# MCU_Schematic.net
KiCad netlist of a schematic drawn in Altium Designer
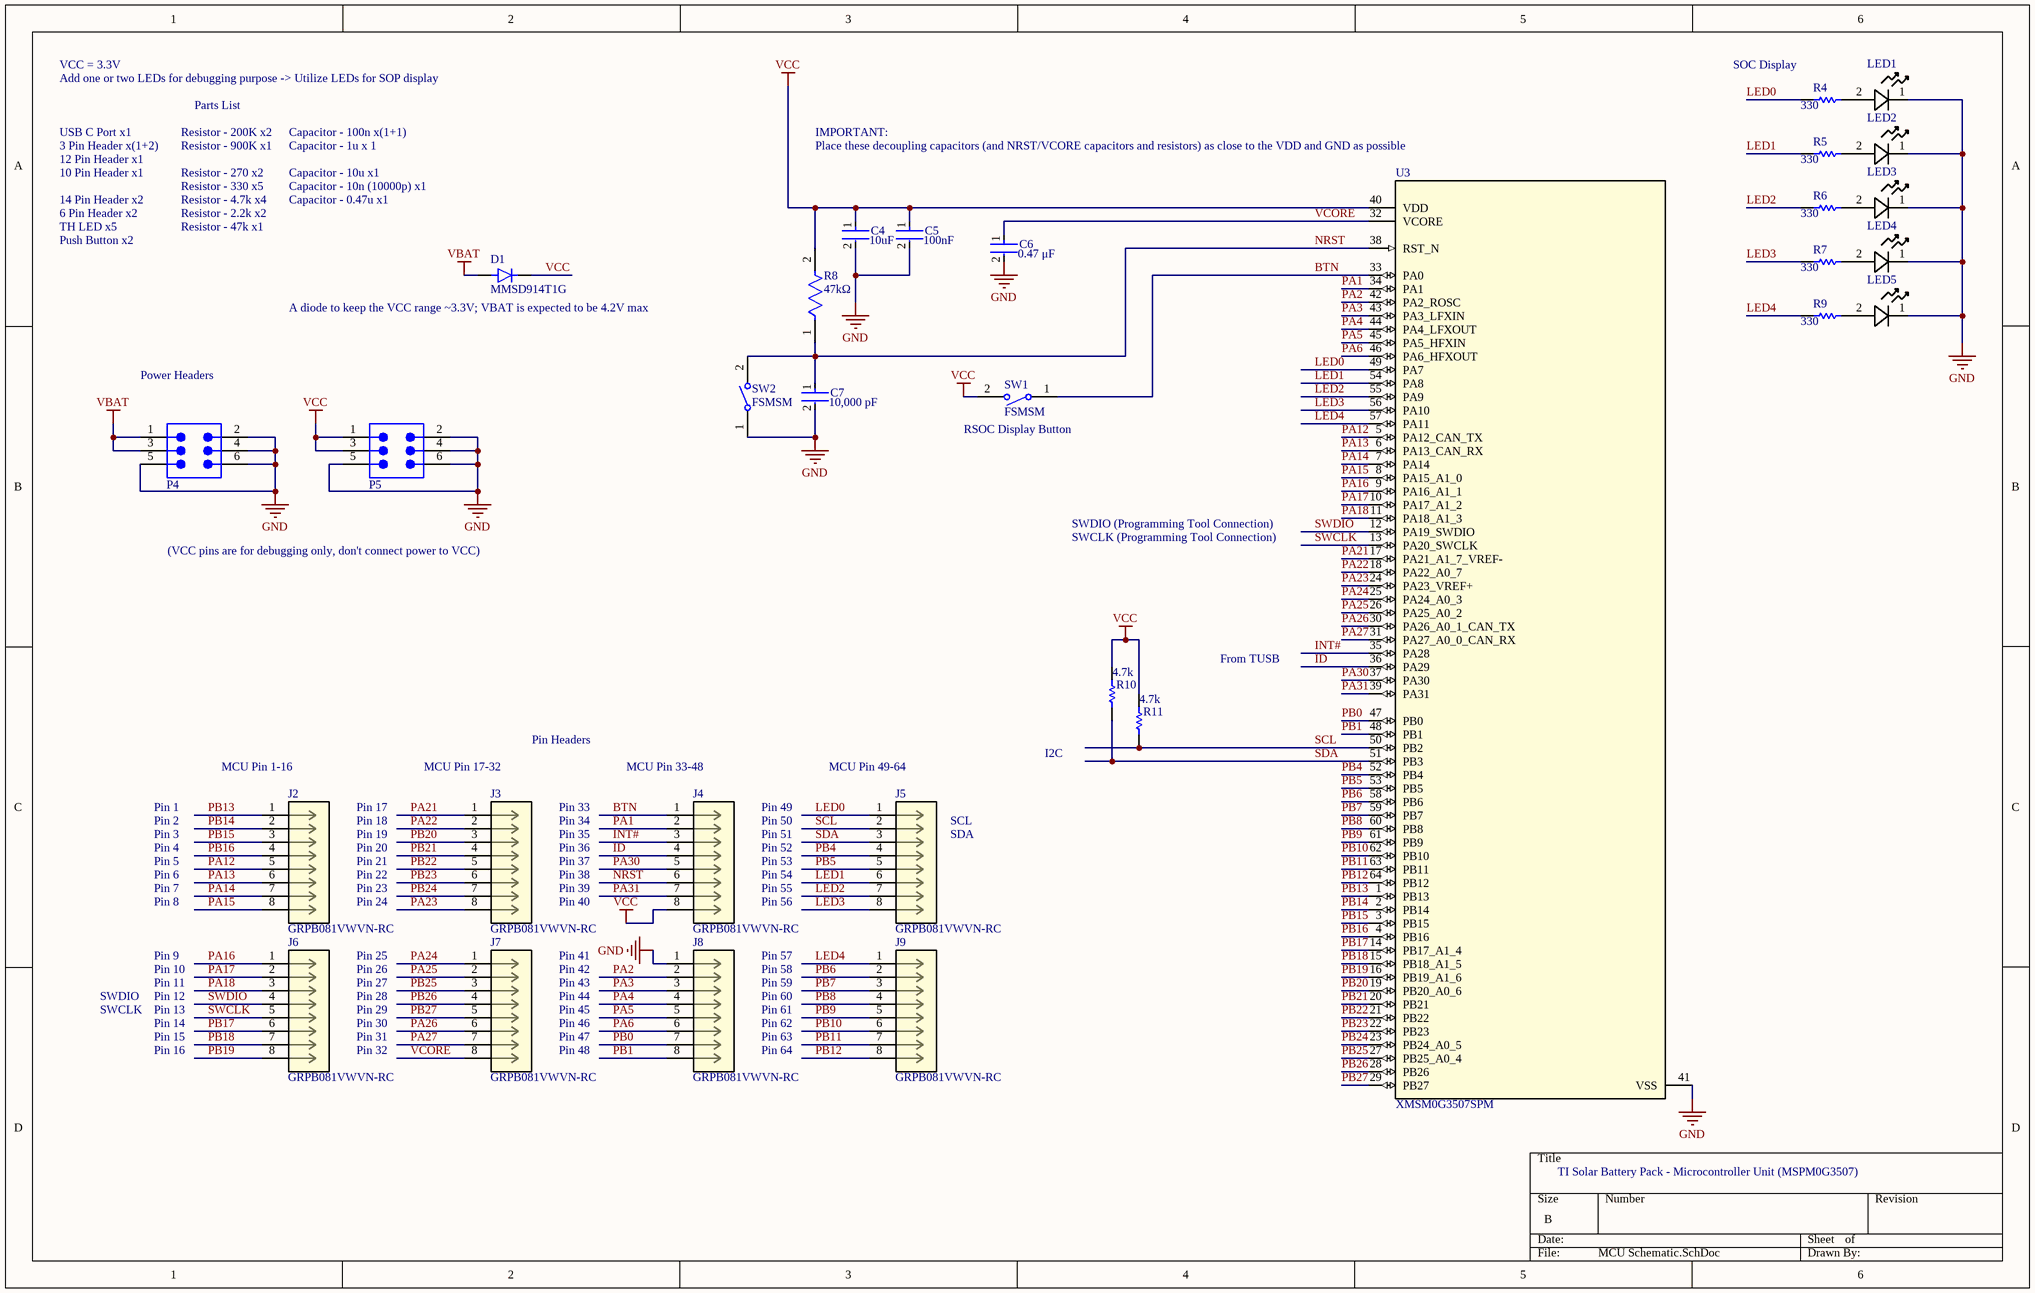
[diagram p0: MCU Schematic.SchDoc]

(export (version "E")
  (design (tool "Eeschema 10.0.6"))
  (components
    (comp (ref "C4")
      (value "C0805C106J8RACAUTO")
      (footprint "FP-C0805C106J8RACAUTO-MFG")
      (description "CAP CER 10UF 10V X7R 0805")
      (fields (field (name "CAPACITANCE") "10uF") (field (name "TOLERANCE") "5%"))
      (libsource (lib "Altium Content Vault") (part "02cd4be3c70576c341d710602a673aa"))
    )
    (comp (ref "C5")
      (value "GRMJN65C1H104GE01J")
      (footprint "FP-GRMJN6-0_1-MFG")
      (description "GRMJN65C1H104GE01J Multilayer Ceramic Capacitor, 0.1 uF, 50 V, ± 2%, C0G (NP0), 0704 [1810 Metric]")
      (fields (field (name "TOLERANCE") "2%") (field (name "CAPACITANCE") "100nF"))
      (libsource (lib "Altium Content Vault") (part "02cd4be3c70576c341d710602a673aa"))
    )
    (comp (ref "C6")
      (value "0.47 μF")
      (footprint "FP-C0603C-CF-MFG")
      (description "CAP CER 0.47UF 16V X7R 0603")
      (fields
        (field (name "MANUFACTURER PART NUMBER") "C0603C474J4RACTU")
        (field (name "MANUFACTURER") "KEMET")
      )
      (libsource (lib "Altium Content Vault") (part "b4654b650e69147ec39a6b967a45e02"))
    )
    (comp (ref "C7")
      (value "10,000 pF")
      (footprint "FP-C0603C-CF-MFG")
      (description "Capacitor; Ceramic; Cap; .010uF; Tol 5%; SMT; Vol-Rtg 50V; X7R; Tape and Reel")
      (fields
        (field (name "OCTOPART") "https://octopart.com/c0603c103j5ractu-kemet-91371")
        (field (name "MANUFACTURER") "KEMET")
      )
      (libsource (lib "Altium Content Vault") (part "b4654b650e69147ec39a6b967a45e02"))
    )
    (comp (ref "D1")
      (value "MMSD914T1G")
      (footprint "DIO_MMSD914T1G")
      (description "Diode Standard 100 V 200mA (DC) Surface Mount SOD-123")
      (fields (field (name "MF") "ON Semiconductor"))
      (libsource (lib "MMSD914T1G") (part "MMSD914T1G"))
    )
    (comp (ref "J2")
      (value "GRPB081VWVN-RC")
      (footprint "CONN8_VWVN-RC_SUL")
      (description "No Description Available")
      (libsource (lib "GRPB081VWVN-RC") (part "GRPB081VWVN-RC"))
    )
    (comp (ref "J3")
      (value "GRPB081VWVN-RC")
      (footprint "CONN8_VWVN-RC_SUL")
      (description "No Description Available")
      (libsource (lib "GRPB081VWVN-RC") (part "GRPB081VWVN-RC"))
    )
    (comp (ref "J4")
      (value "GRPB081VWVN-RC")
      (footprint "CONN8_VWVN-RC_SUL")
      (description "No Description Available")
      (libsource (lib "GRPB081VWVN-RC") (part "GRPB081VWVN-RC"))
    )
    (comp (ref "J5")
      (value "GRPB081VWVN-RC")
      (footprint "CONN8_VWVN-RC_SUL")
      (description "No Description Available")
      (libsource (lib "GRPB081VWVN-RC") (part "GRPB081VWVN-RC"))
    )
    (comp (ref "J6")
      (value "GRPB081VWVN-RC")
      (footprint "CONN8_VWVN-RC_SUL")
      (description "No Description Available")
      (libsource (lib "GRPB081VWVN-RC") (part "GRPB081VWVN-RC"))
    )
    (comp (ref "J7")
      (value "GRPB081VWVN-RC")
      (footprint "CONN8_VWVN-RC_SUL")
      (description "No Description Available")
      (libsource (lib "GRPB081VWVN-RC") (part "GRPB081VWVN-RC"))
    )
    (comp (ref "J8")
      (value "GRPB081VWVN-RC")
      (footprint "CONN8_VWVN-RC_SUL")
      (description "No Description Available")
      (libsource (lib "GRPB081VWVN-RC") (part "GRPB081VWVN-RC"))
    )
    (comp (ref "J9")
      (value "GRPB081VWVN-RC")
      (footprint "CONN8_VWVN-RC_SUL")
      (description "No Description Available")
      (libsource (lib "GRPB081VWVN-RC") (part "GRPB081VWVN-RC"))
    )
    (comp (ref "LED1")
      (value "LTW-420D7")
      (footprint "LED_LTW-420D7_LTO")
      (description "No Description Available")
      (libsource (lib "LTW-420D7") (part "LTW-420D7"))
    )
    (comp (ref "LED2")
      (value "LTW-420D7")
      (footprint "LED_LTW-420D7_LTO")
      (description "No Description Available")
      (libsource (lib "LTW-420D7") (part "LTW-420D7"))
    )
    (comp (ref "LED3")
      (value "LTW-420D7")
      (footprint "LED_LTW-420D7_LTO")
      (description "No Description Available")
      (libsource (lib "LTW-420D7") (part "LTW-420D7"))
    )
    (comp (ref "LED4")
      (value "LTW-420D7")
      (footprint "LED_LTW-420D7_LTO")
      (description "No Description Available")
      (libsource (lib "LTW-420D7") (part "LTW-420D7"))
    )
    (comp (ref "LED5")
      (value "LTW-420D7")
      (footprint "LED_LTW-420D7_LTO")
      (description "No Description Available")
      (libsource (lib "LTW-420D7") (part "LTW-420D7"))
    )
    (comp (ref "P4")
      (value "61000621121")
      (footprint "61000621121")
      (description "WR-PHD Pin Header, SMT, Vertical, pitch 2.54mm, 2 Row, 6P")
      (fields (field (name "MANUFACTURER") "Wurth Elektronik"))
      (libsource (lib "Altium_WR-PHD_rev24a") (part "61000621121"))
    )
    (comp (ref "P5")
      (value "61000621121")
      (footprint "61000621121")
      (description "WR-PHD Pin Header, SMT, Vertical, pitch 2.54mm, 2 Row, 6P")
      (fields (field (name "MANUFACTURER") "Wurth Elektronik"))
      (libsource (lib "Altium_WR-PHD_rev24a") (part "61000621121"))
    )
    (comp (ref "R4")
      (value "330")
      (footprint "RESC2013X60X40LL20T25")
      (fields (field (name "MANUFACTURER") "Panasonic") (field (name "PART NUMBER") "ERA6AEB331V"))
      (libsource (lib "Altium Content Vault") (part "RES"))
    )
    (comp (ref "R5")
      (value "330")
      (footprint "RESC2013X60X40LL20T25")
      (fields (field (name "MANUFACTURER") "Panasonic") (field (name "PART NUMBER") "ERA6AEB331V"))
      (libsource (lib "Altium Content Vault") (part "RES"))
    )
    (comp (ref "R6")
      (value "330")
      (footprint "RESC2013X60X40LL20T25")
      (fields (field (name "MANUFACTURER") "Panasonic") (field (name "PART NUMBER") "ERA6AEB331V"))
      (libsource (lib "Altium Content Vault") (part "RES"))
    )
    (comp (ref "R7")
      (value "330")
      (footprint "RESC2013X60X40LL20T25")
      (fields (field (name "MANUFACTURER") "Panasonic") (field (name "PART NUMBER") "ERA6AEB331V"))
      (libsource (lib "Altium Content Vault") (part "RES"))
    )
    (comp (ref "R8")
      (value "ERA-6AEB473V")
      (footprint "FP-ERA6A-MFG")
      (fields (field (name "RESISTANCE") "47kΩ") (field (name "TOLERANCE") "0.1%"))
      (libsource (lib "Altium Content Vault") (part "1029c3af85768c4190bb7ad29bc67b5"))
    )
    (comp (ref "R9")
      (value "330")
      (footprint "RESC2013X60X40LL20T25")
      (fields (field (name "MANUFACTURER") "Panasonic") (field (name "PART NUMBER") "ERA6AEB331V"))
      (libsource (lib "Altium Content Vault") (part "RES"))
    )
    (comp (ref "R10")
      (value "4.7k")
      (footprint "RESC2013X60X40ML20T25")
      (fields
        (field (name "PART NUMBER") "ERA6AEB472V")
        (field (name "MANUFACTURER") "Panasonic")
        (field (name "MANUFACTURER PART NUMBER") "ERA-6AEB472V")
      )
      (libsource (lib "Altium Content Vault") (part "RES"))
    )
    (comp (ref "R11")
      (value "4.7k")
      (footprint "RESC2013X60X40ML20T25")
      (fields
        (field (name "PART NUMBER") "ERA6AEB472V")
        (field (name "MANUFACTURER") "Panasonic")
        (field (name "MANUFACTURER PART NUMBER") "ERA-6AEB472V")
      )
      (libsource (lib "Altium Content Vault") (part "RES"))
    )
    (comp (ref "SW1")
      (value "FSMSM")
      (footprint "TECO-FSMSM-2_V")
      (description "FSMSM Push Button Switch, 50 mA, -35 to 85 degC, 2-Pin SMD, RoHS, Bulk")
      (fields (field (name "MANUFACTURER") "TE Connectivity"))
      (libsource (lib "Altium Content Vault") (part "SW-SPST-2_C"))
    )
    (comp (ref "SW2")
      (value "FSMSM")
      (footprint "TECO-FSMSM-2_V")
      (description "FSMSM Push Button Switch, 50 mA, -35 to 85 degC, 2-Pin SMD, RoHS, Bulk")
      (fields (field (name "MANUFACTURER") "TE Connectivity"))
      (libsource (lib "Altium Content Vault") (part "SW-SPST-2_C"))
    )
    (comp (ref "U3")
      (value "XMSM0G3507SPM")
      (footprint "PM0064A-IPC_A")
      (description "No Description Available")
      (libsource (lib "XMSM0G3507SPM") (part "XMSM0G3507SPM"))
    )
  )
  (nets
    (net (code "1") (name "/BTN") (class "Default")
      (node (ref "J4") (pin "1") (pinfunction "1_1") (pintype "passive"))
      (node (ref "SW1") (pin "1") (pinfunction "1_1") (pintype "passive"))
      (node (ref "U3") (pin "33") (pinfunction "PA0_33") (pintype "bidirectional"))
    )
    (net (code "2") (name "/ID") (class "Default")
      (node (ref "J4") (pin "4") (pinfunction "4_4") (pintype "passive"))
      (node (ref "U3") (pin "36") (pinfunction "PA29_36") (pintype "bidirectional"))
    )
    (net (code "3") (name "/INT#") (class "Default")
      (node (ref "J4") (pin "3") (pinfunction "3_3") (pintype "passive"))
      (node (ref "U3") (pin "35") (pinfunction "PA28_35") (pintype "bidirectional"))
    )
    (net (code "4") (name "/LED0") (class "Default")
      (node (ref "J5") (pin "1") (pinfunction "1_1") (pintype "passive"))
      (node (ref "R4") (pin "1") (pinfunction "1_1") (pintype "passive"))
      (node (ref "U3") (pin "49") (pinfunction "PA7_49") (pintype "bidirectional"))
    )
    (net (code "5") (name "/LED1") (class "Default")
      (node (ref "J5") (pin "6") (pinfunction "6_6") (pintype "passive"))
      (node (ref "R5") (pin "1") (pinfunction "1_1") (pintype "passive"))
      (node (ref "U3") (pin "54") (pinfunction "PA8_54") (pintype "bidirectional"))
    )
    (net (code "6") (name "/LED2") (class "Default")
      (node (ref "J5") (pin "7") (pinfunction "7_7") (pintype "passive"))
      (node (ref "R6") (pin "1") (pinfunction "1_1") (pintype "passive"))
      (node (ref "U3") (pin "55") (pinfunction "PA9_55") (pintype "bidirectional"))
    )
    (net (code "7") (name "/LED3") (class "Default")
      (node (ref "J5") (pin "8") (pinfunction "8_8") (pintype "passive"))
      (node (ref "R7") (pin "1") (pinfunction "1_1") (pintype "passive"))
      (node (ref "U3") (pin "56") (pinfunction "PA10_56") (pintype "bidirectional"))
    )
    (net (code "8") (name "/LED4") (class "Default")
      (node (ref "J9") (pin "1") (pinfunction "1_1") (pintype "passive"))
      (node (ref "R9") (pin "1") (pinfunction "1_1") (pintype "passive"))
      (node (ref "U3") (pin "57") (pinfunction "PA11_57") (pintype "bidirectional"))
    )
    (net (code "9") (name "/NRST") (class "Default")
      (node (ref "C7") (pin "1") (pinfunction "1_1") (pintype "passive"))
      (node (ref "J4") (pin "6") (pinfunction "6_6") (pintype "passive"))
      (node (ref "R8") (pin "1") (pinfunction "1_1") (pintype "passive"))
      (node (ref "SW2") (pin "2") (pinfunction "2_2") (pintype "passive"))
      (node (ref "U3") (pin "38") (pinfunction "RST_N_38") (pintype "input"))
    )
    (net (code "10") (name "/PA1") (class "Default")
      (node (ref "J4") (pin "2") (pinfunction "2_2") (pintype "passive"))
      (node (ref "U3") (pin "34") (pinfunction "PA1_34") (pintype "bidirectional"))
    )
    (net (code "11") (name "/PA2") (class "Default")
      (node (ref "J8") (pin "2") (pinfunction "2_2") (pintype "passive"))
      (node (ref "U3") (pin "42") (pinfunction "PA2_ROSC_42") (pintype "bidirectional"))
    )
    (net (code "12") (name "/PA3") (class "Default")
      (node (ref "J8") (pin "3") (pinfunction "3_3") (pintype "passive"))
      (node (ref "U3") (pin "43") (pinfunction "PA3_LFXIN_43") (pintype "bidirectional"))
    )
    (net (code "13") (name "/PA4") (class "Default")
      (node (ref "J8") (pin "4") (pinfunction "4_4") (pintype "passive"))
      (node (ref "U3") (pin "44") (pinfunction "PA4_LFXOUT_44") (pintype "bidirectional"))
    )
    (net (code "14") (name "/PA5") (class "Default")
      (node (ref "J8") (pin "5") (pinfunction "5_5") (pintype "passive"))
      (node (ref "U3") (pin "45") (pinfunction "PA5_HFXIN_45") (pintype "bidirectional"))
    )
    (net (code "15") (name "/PA6") (class "Default")
      (node (ref "J8") (pin "6") (pinfunction "6_6") (pintype "passive"))
      (node (ref "U3") (pin "46") (pinfunction "PA6_HFXOUT_46") (pintype "bidirectional"))
    )
    (net (code "16") (name "/PA12") (class "Default")
      (node (ref "J2") (pin "5") (pinfunction "5_5") (pintype "passive"))
      (node (ref "U3") (pin "5") (pinfunction "PA12_CAN_TX_5") (pintype "bidirectional"))
    )
    (net (code "17") (name "/PA13") (class "Default")
      (node (ref "J2") (pin "6") (pinfunction "6_6") (pintype "passive"))
      (node (ref "U3") (pin "6") (pinfunction "PA13_CAN_RX_6") (pintype "bidirectional"))
    )
    (net (code "18") (name "/PA14") (class "Default")
      (node (ref "J2") (pin "7") (pinfunction "7_7") (pintype "passive"))
      (node (ref "U3") (pin "7") (pinfunction "PA14_7") (pintype "bidirectional"))
    )
    (net (code "19") (name "/PA15") (class "Default")
      (node (ref "J2") (pin "8") (pinfunction "8_8") (pintype "passive"))
      (node (ref "U3") (pin "8") (pinfunction "PA15_A1_0_8") (pintype "bidirectional"))
    )
    (net (code "20") (name "/PA16") (class "Default")
      (node (ref "J6") (pin "1") (pinfunction "1_1") (pintype "passive"))
      (node (ref "U3") (pin "9") (pinfunction "PA16_A1_1_9") (pintype "bidirectional"))
    )
    (net (code "21") (name "/PA17") (class "Default")
      (node (ref "J6") (pin "2") (pinfunction "2_2") (pintype "passive"))
      (node (ref "U3") (pin "10") (pinfunction "PA17_A1_2_10") (pintype "bidirectional"))
    )
    (net (code "22") (name "/PA18") (class "Default")
      (node (ref "J6") (pin "3") (pinfunction "3_3") (pintype "passive"))
      (node (ref "U3") (pin "11") (pinfunction "PA18_A1_3_11") (pintype "bidirectional"))
    )
    (net (code "23") (name "/PA21") (class "Default")
      (node (ref "J3") (pin "1") (pinfunction "1_1") (pintype "passive"))
      (node (ref "U3") (pin "17") (pinfunction "PA21_A1_7_VREF-_17") (pintype "bidirectional"))
    )
    (net (code "24") (name "/PA22") (class "Default")
      (node (ref "J3") (pin "2") (pinfunction "2_2") (pintype "passive"))
      (node (ref "U3") (pin "18") (pinfunction "PA22_A0_7_18") (pintype "bidirectional"))
    )
    (net (code "25") (name "/PA23") (class "Default")
      (node (ref "J3") (pin "8") (pinfunction "8_8") (pintype "passive"))
      (node (ref "U3") (pin "24") (pinfunction "PA23_VREF+_24") (pintype "bidirectional"))
    )
    (net (code "26") (name "/PA24") (class "Default")
      (node (ref "J7") (pin "1") (pinfunction "1_1") (pintype "passive"))
      (node (ref "U3") (pin "25") (pinfunction "PA24_A0_3_25") (pintype "bidirectional"))
    )
    (net (code "27") (name "/PA25") (class "Default")
      (node (ref "J7") (pin "2") (pinfunction "2_2") (pintype "passive"))
      (node (ref "U3") (pin "26") (pinfunction "PA25_A0_2_26") (pintype "bidirectional"))
    )
    (net (code "28") (name "/PA26") (class "Default")
      (node (ref "J7") (pin "6") (pinfunction "6_6") (pintype "passive"))
      (node (ref "U3") (pin "30") (pinfunction "PA26_A0_1_CAN_TX_30") (pintype "bidirectional"))
    )
    (net (code "29") (name "/PA27") (class "Default")
      (node (ref "J7") (pin "7") (pinfunction "7_7") (pintype "passive"))
      (node (ref "U3") (pin "31") (pinfunction "PA27_A0_0_CAN_RX_31") (pintype "bidirectional"))
    )
    (net (code "30") (name "/PA30") (class "Default")
      (node (ref "J4") (pin "5") (pinfunction "5_5") (pintype "passive"))
      (node (ref "U3") (pin "37") (pinfunction "PA30_37") (pintype "bidirectional"))
    )
    (net (code "31") (name "/PA31") (class "Default")
      (node (ref "J4") (pin "7") (pinfunction "7_7") (pintype "passive"))
      (node (ref "U3") (pin "39") (pinfunction "PA31_39") (pintype "bidirectional"))
    )
    (net (code "32") (name "/PB0") (class "Default")
      (node (ref "J8") (pin "7") (pinfunction "7_7") (pintype "passive"))
      (node (ref "U3") (pin "47") (pinfunction "PB0_47") (pintype "bidirectional"))
    )
    (net (code "33") (name "/PB1") (class "Default")
      (node (ref "J8") (pin "8") (pinfunction "8_8") (pintype "passive"))
      (node (ref "U3") (pin "48") (pinfunction "PB1_48") (pintype "bidirectional"))
    )
    (net (code "34") (name "/PB4") (class "Default")
      (node (ref "J5") (pin "4") (pinfunction "4_4") (pintype "passive"))
      (node (ref "U3") (pin "52") (pinfunction "PB4_52") (pintype "bidirectional"))
    )
    (net (code "35") (name "/PB5") (class "Default")
      (node (ref "J5") (pin "5") (pinfunction "5_5") (pintype "passive"))
      (node (ref "U3") (pin "53") (pinfunction "PB5_53") (pintype "bidirectional"))
    )
    (net (code "36") (name "/PB6") (class "Default")
      (node (ref "J9") (pin "2") (pinfunction "2_2") (pintype "passive"))
      (node (ref "U3") (pin "58") (pinfunction "PB6_58") (pintype "bidirectional"))
    )
    (net (code "37") (name "/PB7") (class "Default")
      (node (ref "J9") (pin "3") (pinfunction "3_3") (pintype "passive"))
      (node (ref "U3") (pin "59") (pinfunction "PB7_59") (pintype "bidirectional"))
    )
    (net (code "38") (name "/PB8") (class "Default")
      (node (ref "J9") (pin "4") (pinfunction "4_4") (pintype "passive"))
      (node (ref "U3") (pin "60") (pinfunction "PB8_60") (pintype "bidirectional"))
    )
    (net (code "39") (name "/PB9") (class "Default")
      (node (ref "J9") (pin "5") (pinfunction "5_5") (pintype "passive"))
      (node (ref "U3") (pin "61") (pinfunction "PB9_61") (pintype "bidirectional"))
    )
    (net (code "40") (name "/PB10") (class "Default")
      (node (ref "J9") (pin "6") (pinfunction "6_6") (pintype "passive"))
      (node (ref "U3") (pin "62") (pinfunction "PB10_62") (pintype "bidirectional"))
    )
    (net (code "41") (name "/PB11") (class "Default")
      (node (ref "J9") (pin "7") (pinfunction "7_7") (pintype "passive"))
      (node (ref "U3") (pin "63") (pinfunction "PB11_63") (pintype "bidirectional"))
    )
    (net (code "42") (name "/PB12") (class "Default")
      (node (ref "J9") (pin "8") (pinfunction "8_8") (pintype "passive"))
      (node (ref "U3") (pin "64") (pinfunction "PB12_64") (pintype "bidirectional"))
    )
    (net (code "43") (name "/PB13") (class "Default")
      (node (ref "J2") (pin "1") (pinfunction "1_1") (pintype "passive"))
      (node (ref "U3") (pin "1") (pinfunction "PB13_1") (pintype "bidirectional"))
    )
    (net (code "44") (name "/PB14") (class "Default")
      (node (ref "J2") (pin "2") (pinfunction "2_2") (pintype "passive"))
      (node (ref "U3") (pin "2") (pinfunction "PB14_2") (pintype "bidirectional"))
    )
    (net (code "45") (name "/PB15") (class "Default")
      (node (ref "J2") (pin "3") (pinfunction "3_3") (pintype "passive"))
      (node (ref "U3") (pin "3") (pinfunction "PB15_3") (pintype "bidirectional"))
    )
    (net (code "46") (name "/PB16") (class "Default")
      (node (ref "J2") (pin "4") (pinfunction "4_4") (pintype "passive"))
      (node (ref "U3") (pin "4") (pinfunction "PB16_4") (pintype "bidirectional"))
    )
    (net (code "47") (name "/PB17") (class "Default")
      (node (ref "J6") (pin "6") (pinfunction "6_6") (pintype "passive"))
      (node (ref "U3") (pin "14") (pinfunction "PB17_A1_4_14") (pintype "bidirectional"))
    )
    (net (code "48") (name "/PB18") (class "Default")
      (node (ref "J6") (pin "7") (pinfunction "7_7") (pintype "passive"))
      (node (ref "U3") (pin "15") (pinfunction "PB18_A1_5_15") (pintype "bidirectional"))
    )
    (net (code "49") (name "/PB19") (class "Default")
      (node (ref "J6") (pin "8") (pinfunction "8_8") (pintype "passive"))
      (node (ref "U3") (pin "16") (pinfunction "PB19_A1_6_16") (pintype "bidirectional"))
    )
    (net (code "50") (name "/PB20") (class "Default")
      (node (ref "J3") (pin "3") (pinfunction "3_3") (pintype "passive"))
      (node (ref "U3") (pin "19") (pinfunction "PB20_A0_6_19") (pintype "bidirectional"))
    )
    (net (code "51") (name "/PB21") (class "Default")
      (node (ref "J3") (pin "4") (pinfunction "4_4") (pintype "passive"))
      (node (ref "U3") (pin "20") (pinfunction "PB21_20") (pintype "bidirectional"))
    )
    (net (code "52") (name "/PB22") (class "Default")
      (node (ref "J3") (pin "5") (pinfunction "5_5") (pintype "passive"))
      (node (ref "U3") (pin "21") (pinfunction "PB22_21") (pintype "bidirectional"))
    )
    (net (code "53") (name "/PB23") (class "Default")
      (node (ref "J3") (pin "6") (pinfunction "6_6") (pintype "passive"))
      (node (ref "U3") (pin "22") (pinfunction "PB23_22") (pintype "bidirectional"))
    )
    (net (code "54") (name "/PB24") (class "Default")
      (node (ref "J3") (pin "7") (pinfunction "7_7") (pintype "passive"))
      (node (ref "U3") (pin "23") (pinfunction "PB24_A0_5_23") (pintype "bidirectional"))
    )
    (net (code "55") (name "/PB25") (class "Default")
      (node (ref "J7") (pin "3") (pinfunction "3_3") (pintype "passive"))
      (node (ref "U3") (pin "27") (pinfunction "PB25_A0_4_27") (pintype "bidirectional"))
    )
    (net (code "56") (name "/PB26") (class "Default")
      (node (ref "J7") (pin "4") (pinfunction "4_4") (pintype "passive"))
      (node (ref "U3") (pin "28") (pinfunction "PB26_28") (pintype "bidirectional"))
    )
    (net (code "57") (name "/PB27") (class "Default")
      (node (ref "J7") (pin "5") (pinfunction "5_5") (pintype "passive"))
      (node (ref "U3") (pin "29") (pinfunction "PB27_29") (pintype "bidirectional"))
    )
    (net (code "58") (name "/SCL") (class "Default")
      (node (ref "J5") (pin "2") (pinfunction "2_2") (pintype "passive"))
      (node (ref "R11") (pin "1") (pinfunction "1_1") (pintype "passive"))
      (node (ref "U3") (pin "50") (pinfunction "PB2_50") (pintype "bidirectional"))
    )
    (net (code "59") (name "/SDA") (class "Default")
      (node (ref "J5") (pin "3") (pinfunction "3_3") (pintype "passive"))
      (node (ref "R10") (pin "1") (pinfunction "1_1") (pintype "passive"))
      (node (ref "U3") (pin "51") (pinfunction "PB3_51") (pintype "bidirectional"))
    )
    (net (code "60") (name "/SWCLK") (class "Default")
      (node (ref "J6") (pin "5") (pinfunction "5_5") (pintype "passive"))
      (node (ref "U3") (pin "13") (pinfunction "PA20_SWCLK_13") (pintype "bidirectional"))
    )
    (net (code "61") (name "/SWDIO") (class "Default")
      (node (ref "J6") (pin "4") (pinfunction "4_4") (pintype "passive"))
      (node (ref "U3") (pin "12") (pinfunction "PA19_SWDIO_12") (pintype "bidirectional"))
    )
    (net (code "62") (name "/VCORE") (class "Default")
      (node (ref "C6") (pin "1") (pinfunction "1_1") (pintype "passive"))
      (node (ref "J7") (pin "8") (pinfunction "8_8") (pintype "passive"))
      (node (ref "U3") (pin "32") (pinfunction "VCORE_32") (pintype "power_in"))
    )
    (net (code "63") (name "GND") (class "Default")
      (node (ref "C4") (pin "2") (pinfunction "2_2") (pintype "passive"))
      (node (ref "C5") (pin "2") (pinfunction "2_2") (pintype "passive"))
      (node (ref "C6") (pin "2") (pinfunction "2_2") (pintype "passive"))
      (node (ref "C7") (pin "2") (pinfunction "2_2") (pintype "passive"))
      (node (ref "J8") (pin "1") (pinfunction "1_1") (pintype "passive"))
      (node (ref "LED1") (pin "1") (pinfunction "1_1") (pintype "passive"))
      (node (ref "LED2") (pin "1") (pinfunction "1_1") (pintype "passive"))
      (node (ref "LED3") (pin "1") (pinfunction "1_1") (pintype "passive"))
      (node (ref "LED4") (pin "1") (pinfunction "1_1") (pintype "passive"))
      (node (ref "LED5") (pin "1") (pinfunction "1_1") (pintype "passive"))
      (node (ref "P4") (pin "2") (pinfunction "2_2") (pintype "passive"))
      (node (ref "P4") (pin "4") (pinfunction "4_4") (pintype "passive"))
      (node (ref "P4") (pin "5") (pinfunction "5_5") (pintype "passive"))
      (node (ref "P4") (pin "6") (pinfunction "6_6") (pintype "passive"))
      (node (ref "P5") (pin "2") (pinfunction "2_2") (pintype "passive"))
      (node (ref "P5") (pin "4") (pinfunction "4_4") (pintype "passive"))
      (node (ref "P5") (pin "5") (pinfunction "5_5") (pintype "passive"))
      (node (ref "P5") (pin "6") (pinfunction "6_6") (pintype "passive"))
      (node (ref "SW2") (pin "1") (pinfunction "1_1") (pintype "passive"))
      (node (ref "U3") (pin "41") (pinfunction "VSS_41") (pintype "power_in"))
    )
    (net (code "64") (name "Net-(LED1-Pad2)") (class "Default")
      (node (ref "LED1") (pin "2") (pinfunction "2_2") (pintype "passive"))
      (node (ref "R4") (pin "2") (pinfunction "2_2") (pintype "passive"))
    )
    (net (code "65") (name "Net-(LED2-Pad2)") (class "Default")
      (node (ref "LED2") (pin "2") (pinfunction "2_2") (pintype "passive"))
      (node (ref "R5") (pin "2") (pinfunction "2_2") (pintype "passive"))
    )
    (net (code "66") (name "Net-(LED3-Pad2)") (class "Default")
      (node (ref "LED3") (pin "2") (pinfunction "2_2") (pintype "passive"))
      (node (ref "R6") (pin "2") (pinfunction "2_2") (pintype "passive"))
    )
    (net (code "67") (name "Net-(LED4-Pad2)") (class "Default")
      (node (ref "LED4") (pin "2") (pinfunction "2_2") (pintype "passive"))
      (node (ref "R7") (pin "2") (pinfunction "2_2") (pintype "passive"))
    )
    (net (code "68") (name "Net-(LED5-Pad2)") (class "Default")
      (node (ref "LED5") (pin "2") (pinfunction "2_2") (pintype "passive"))
      (node (ref "R9") (pin "2") (pinfunction "2_2") (pintype "passive"))
    )
    (net (code "69") (name "VBAT") (class "Default")
      (node (ref "D1") (pin "A") (pinfunction "A_A") (pintype "passive"))
      (node (ref "P4") (pin "1") (pinfunction "1_1") (pintype "passive"))
      (node (ref "P4") (pin "3") (pinfunction "3_3") (pintype "passive"))
    )
    (net (code "70") (name "VCC") (class "Default")
      (node (ref "C4") (pin "1") (pinfunction "1_1") (pintype "passive"))
      (node (ref "C5") (pin "1") (pinfunction "1_1") (pintype "passive"))
      (node (ref "D1") (pin "K") (pinfunction "K_K") (pintype "passive"))
      (node (ref "J4") (pin "8") (pinfunction "8_8") (pintype "passive"))
      (node (ref "P5") (pin "1") (pinfunction "1_1") (pintype "passive"))
      (node (ref "P5") (pin "3") (pinfunction "3_3") (pintype "passive"))
      (node (ref "R10") (pin "2") (pinfunction "2_2") (pintype "passive"))
      (node (ref "R11") (pin "2") (pinfunction "2_2") (pintype "passive"))
      (node (ref "R8") (pin "2") (pinfunction "2_2") (pintype "passive"))
      (node (ref "SW1") (pin "2") (pinfunction "2_2") (pintype "passive"))
      (node (ref "U3") (pin "40") (pinfunction "VDD_40") (pintype "power_in"))
    )
  )
)
